# SCH_New-Project_2024-08-22.net
KiCad netlist of a schematic drawn in EasyEDA
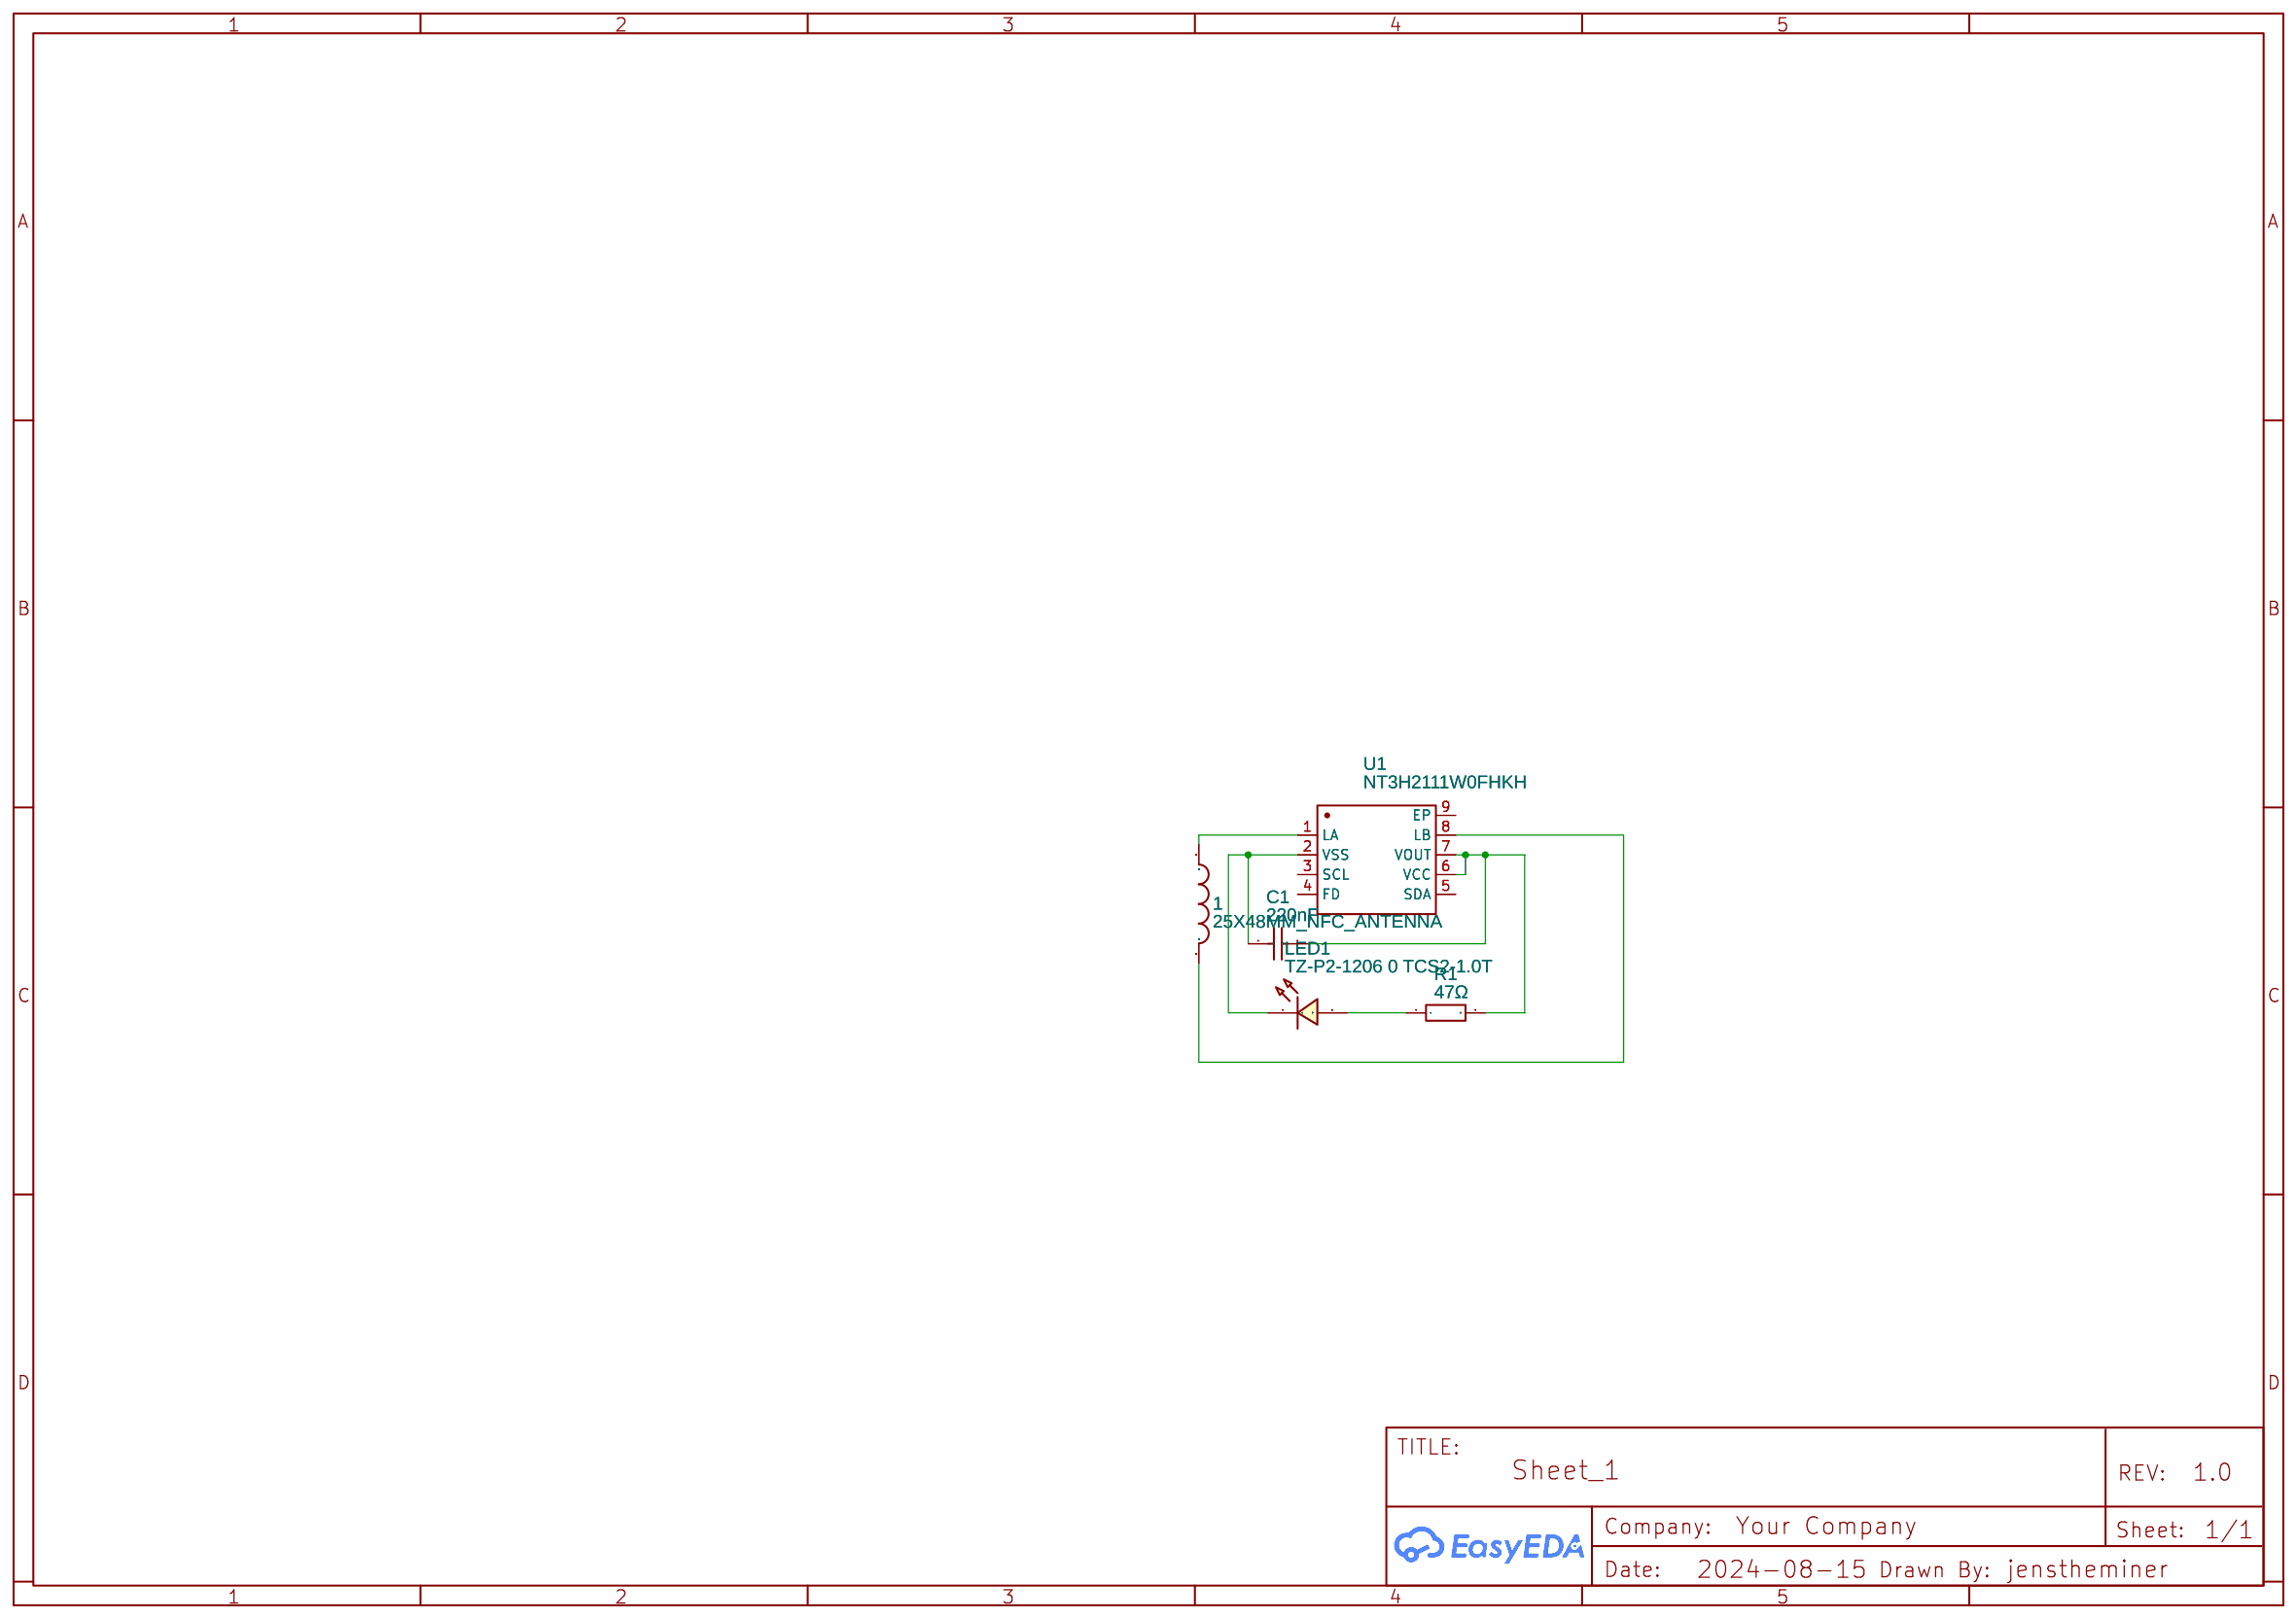
[diagram p0: schematic sheet]

(export (version "E")
  (design (tool "Eeschema 10.0.6"))
  (components
    (comp (ref "1") (value "25X48MM_NFC_ANTENNA") (libsource (lib "") (part "25X48MM_NFC_ANTENNA")))
    (comp (ref "C1")
      (value "220nF")
      (fields
        (field (name "Manufacturer Part") "CL10B224KA8NNNC")
        (field (name "Manufacturer") "SAMSUNG(三星)")
      )
      (libsource (lib "") (part "CL10B224KA8NNNC"))
    )
    (comp (ref "LED1")
      (value "TZ-P2-1206 0 TCS2-1.0T")
      (fields (field (name "Manufacturer") "TUOZHAN(拓展光电)"))
      (libsource (lib "") (part "TZ-P2-1206 0 TCS2-1.0T"))
    )
    (comp (ref "R1")
      (value "47Ω")
      (fields
        (field (name "Manufacturer Part") "0603WAF470JT5E")
        (field (name "Manufacturer") "UNI-ROYAL(厚声)")
      )
      (libsource (lib "") (part "0603WAF470JT5E"))
    )
    (comp (ref "U1")
      (value "NT3H2111W0FHKH")
      (fields (field (name "Manufacturer") "NXP(恩智浦)"))
      (libsource (lib "") (part "NT3H2111W0FHKH"))
    )
  )
  (nets
    (net (code "1") (name "Net-(LED1-Pad2)") (class "Default")
      (node (ref "LED1") (pin "2") (pinfunction "2_2") (pintype "unspecified"))
      (node (ref "R1") (pin "1") (pinfunction "1_1") (pintype "input"))
    )
    (net (code "2") (name "Net-(U1-LA)") (class "Default")
      (node (ref "1") (pin "P$1") (pinfunction "P$1_P$1") (pintype "bidirectional"))
      (node (ref "U1") (pin "1") (pinfunction "LA_1") (pintype "unspecified"))
    )
    (net (code "3") (name "Net-(U1-LB)") (class "Default")
      (node (ref "1") (pin "P$2") (pinfunction "P$2_P$2") (pintype "bidirectional"))
      (node (ref "U1") (pin "8") (pinfunction "LB_8") (pintype "unspecified"))
    )
    (net (code "4") (name "Net-(U1-VCC)") (class "Default")
      (node (ref "C1") (pin "2") (pinfunction "2_2") (pintype "input"))
      (node (ref "R1") (pin "2") (pinfunction "2_2") (pintype "input"))
      (node (ref "U1") (pin "6") (pinfunction "VCC_6") (pintype "unspecified"))
      (node (ref "U1") (pin "7") (pinfunction "VOUT_7") (pintype "unspecified"))
    )
    (net (code "5") (name "Net-(U1-VSS)") (class "Default")
      (node (ref "C1") (pin "1") (pinfunction "1_1") (pintype "input"))
      (node (ref "LED1") (pin "1") (pinfunction "1_1") (pintype "unspecified"))
      (node (ref "U1") (pin "2") (pinfunction "VSS_2") (pintype "unspecified"))
    )
    (net (code "6") (name "unconnected-(U1-EP-Pad9)") (class "Default")
      (node (ref "U1") (pin "9") (pinfunction "EP_9") (pintype "unspecified"))
    )
    (net (code "7") (name "unconnected-(U1-FD-Pad4)") (class "Default")
      (node (ref "U1") (pin "4") (pinfunction "FD_4") (pintype "unspecified"))
    )
    (net (code "8") (name "unconnected-(U1-SCL-Pad3)") (class "Default")
      (node (ref "U1") (pin "3") (pinfunction "SCL_3") (pintype "unspecified"))
    )
    (net (code "9") (name "unconnected-(U1-SDA-Pad5)") (class "Default")
      (node (ref "U1") (pin "5") (pinfunction "SDA_5") (pintype "unspecified"))
    )
  )
)
